# 06_-_Backlight_LEDs.net
KiCad netlist of a schematic drawn in Altium Designer
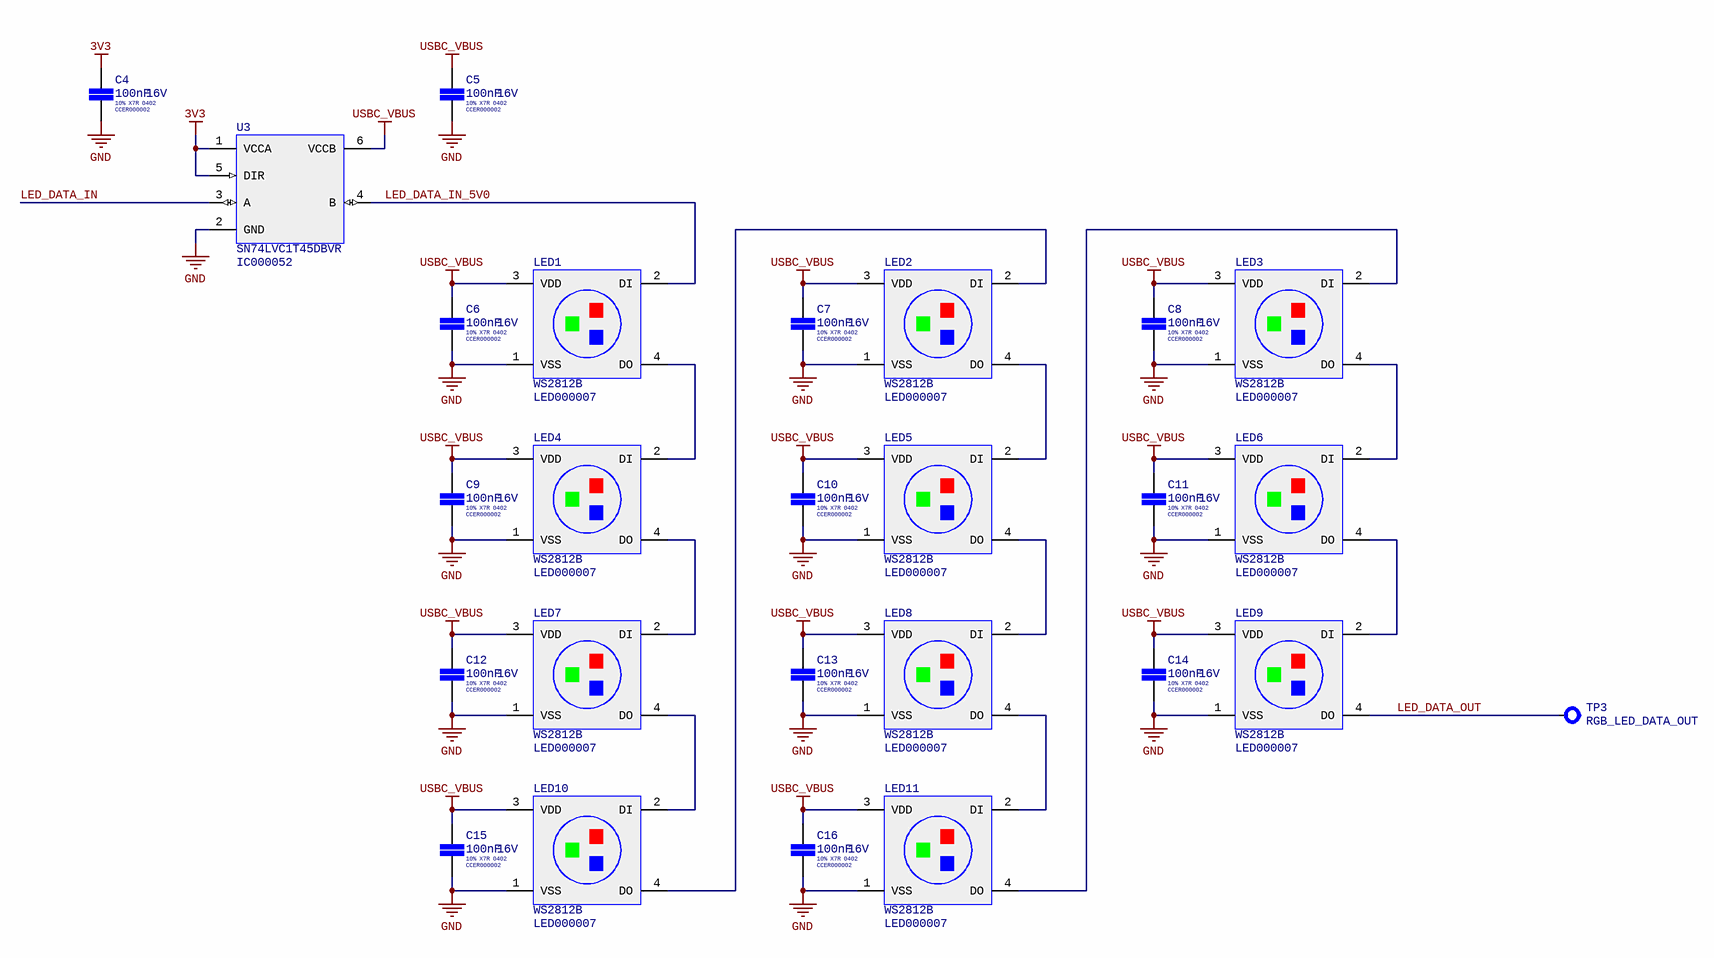
[diagram p0: [06] - Backlight LEDs.SchDoc]

(export (version "E")
  (design (tool "Eeschema 10.0.6"))
  (components
    (comp (ref "C4")
      (value "100nF 16V")
      (footprint "CAP-SMD-0402-0.55MM-IPC-MED")
      (description "CAP CER 100N 16V X7R 10% SMD 0402 125C SAMSUNG")
      (fields
        (field (name "VOLTAGE") "16V")
        (field (name "TOLERANCE") "10%")
        (field (name "INTERNAL PART NUMBER") "CCER000002")
        (field (name "VOLTAGE RATING (DC)") "16V")
        (field (name "DIELECTRIC") "X7R")
        (field (name "CASE/PACKAGE") "0402")
        (field (name "CAPACITANCE") "100nF")
      )
      (libsource (lib "Altium_Lib_Standard") (part "CL05B104KO5NNNC"))
    )
    (comp (ref "C5")
      (value "100nF 16V")
      (footprint "CAP-SMD-0402-0.55MM-IPC-MED")
      (description "CAP CER 100N 16V X7R 10% SMD 0402 125C SAMSUNG")
      (fields
        (field (name "VOLTAGE") "16V")
        (field (name "TOLERANCE") "10%")
        (field (name "INTERNAL PART NUMBER") "CCER000002")
        (field (name "VOLTAGE RATING (DC)") "16V")
        (field (name "DIELECTRIC") "X7R")
        (field (name "CASE/PACKAGE") "0402")
        (field (name "CAPACITANCE") "100nF")
      )
      (libsource (lib "Altium_Lib_Standard") (part "CL05B104KO5NNNC"))
    )
    (comp (ref "C6")
      (value "100nF 16V")
      (footprint "CAP-SMD-0402-0.55MM-IPC-MED")
      (description "CAP CER 100N 16V X7R 10% SMD 0402 125C SAMSUNG")
      (fields
        (field (name "VOLTAGE") "16V")
        (field (name "TOLERANCE") "10%")
        (field (name "INTERNAL PART NUMBER") "CCER000002")
        (field (name "VOLTAGE RATING (DC)") "16V")
        (field (name "DIELECTRIC") "X7R")
        (field (name "CASE/PACKAGE") "0402")
        (field (name "CAPACITANCE") "100nF")
      )
      (libsource (lib "Altium_Lib_Standard") (part "CL05B104KO5NNNC"))
    )
    (comp (ref "C7")
      (value "100nF 16V")
      (footprint "CAP-SMD-0402-0.55MM-IPC-MED")
      (description "CAP CER 100N 16V X7R 10% SMD 0402 125C SAMSUNG")
      (fields
        (field (name "VOLTAGE") "16V")
        (field (name "TOLERANCE") "10%")
        (field (name "INTERNAL PART NUMBER") "CCER000002")
        (field (name "VOLTAGE RATING (DC)") "16V")
        (field (name "DIELECTRIC") "X7R")
        (field (name "CASE/PACKAGE") "0402")
        (field (name "CAPACITANCE") "100nF")
      )
      (libsource (lib "Altium_Lib_Standard") (part "CL05B104KO5NNNC"))
    )
    (comp (ref "C8")
      (value "100nF 16V")
      (footprint "CAP-SMD-0402-0.55MM-IPC-MED")
      (description "CAP CER 100N 16V X7R 10% SMD 0402 125C SAMSUNG")
      (fields
        (field (name "VOLTAGE") "16V")
        (field (name "TOLERANCE") "10%")
        (field (name "INTERNAL PART NUMBER") "CCER000002")
        (field (name "VOLTAGE RATING (DC)") "16V")
        (field (name "DIELECTRIC") "X7R")
        (field (name "CASE/PACKAGE") "0402")
        (field (name "CAPACITANCE") "100nF")
      )
      (libsource (lib "Altium_Lib_Standard") (part "CL05B104KO5NNNC"))
    )
    (comp (ref "C9")
      (value "100nF 16V")
      (footprint "CAP-SMD-0402-0.55MM-IPC-MED")
      (description "CAP CER 100N 16V X7R 10% SMD 0402 125C SAMSUNG")
      (fields
        (field (name "VOLTAGE") "16V")
        (field (name "TOLERANCE") "10%")
        (field (name "INTERNAL PART NUMBER") "CCER000002")
        (field (name "VOLTAGE RATING (DC)") "16V")
        (field (name "DIELECTRIC") "X7R")
        (field (name "CASE/PACKAGE") "0402")
        (field (name "CAPACITANCE") "100nF")
      )
      (libsource (lib "Altium_Lib_Standard") (part "CL05B104KO5NNNC"))
    )
    (comp (ref "C10")
      (value "100nF 16V")
      (footprint "CAP-SMD-0402-0.55MM-IPC-MED")
      (description "CAP CER 100N 16V X7R 10% SMD 0402 125C SAMSUNG")
      (fields
        (field (name "VOLTAGE") "16V")
        (field (name "TOLERANCE") "10%")
        (field (name "INTERNAL PART NUMBER") "CCER000002")
        (field (name "VOLTAGE RATING (DC)") "16V")
        (field (name "DIELECTRIC") "X7R")
        (field (name "CASE/PACKAGE") "0402")
        (field (name "CAPACITANCE") "100nF")
      )
      (libsource (lib "Altium_Lib_Standard") (part "CL05B104KO5NNNC"))
    )
    (comp (ref "C11")
      (value "100nF 16V")
      (footprint "CAP-SMD-0402-0.55MM-IPC-MED")
      (description "CAP CER 100N 16V X7R 10% SMD 0402 125C SAMSUNG")
      (fields
        (field (name "VOLTAGE") "16V")
        (field (name "TOLERANCE") "10%")
        (field (name "INTERNAL PART NUMBER") "CCER000002")
        (field (name "VOLTAGE RATING (DC)") "16V")
        (field (name "DIELECTRIC") "X7R")
        (field (name "CASE/PACKAGE") "0402")
        (field (name "CAPACITANCE") "100nF")
      )
      (libsource (lib "Altium_Lib_Standard") (part "CL05B104KO5NNNC"))
    )
    (comp (ref "C12")
      (value "100nF 16V")
      (footprint "CAP-SMD-0402-0.55MM-IPC-MED")
      (description "CAP CER 100N 16V X7R 10% SMD 0402 125C SAMSUNG")
      (fields
        (field (name "VOLTAGE") "16V")
        (field (name "TOLERANCE") "10%")
        (field (name "INTERNAL PART NUMBER") "CCER000002")
        (field (name "VOLTAGE RATING (DC)") "16V")
        (field (name "DIELECTRIC") "X7R")
        (field (name "CASE/PACKAGE") "0402")
        (field (name "CAPACITANCE") "100nF")
      )
      (libsource (lib "Altium_Lib_Standard") (part "CL05B104KO5NNNC"))
    )
    (comp (ref "C13")
      (value "100nF 16V")
      (footprint "CAP-SMD-0402-0.55MM-IPC-MED")
      (description "CAP CER 100N 16V X7R 10% SMD 0402 125C SAMSUNG")
      (fields
        (field (name "VOLTAGE") "16V")
        (field (name "TOLERANCE") "10%")
        (field (name "INTERNAL PART NUMBER") "CCER000002")
        (field (name "VOLTAGE RATING (DC)") "16V")
        (field (name "DIELECTRIC") "X7R")
        (field (name "CASE/PACKAGE") "0402")
        (field (name "CAPACITANCE") "100nF")
      )
      (libsource (lib "Altium_Lib_Standard") (part "CL05B104KO5NNNC"))
    )
    (comp (ref "C14")
      (value "100nF 16V")
      (footprint "CAP-SMD-0402-0.55MM-IPC-MED")
      (description "CAP CER 100N 16V X7R 10% SMD 0402 125C SAMSUNG")
      (fields
        (field (name "VOLTAGE") "16V")
        (field (name "TOLERANCE") "10%")
        (field (name "INTERNAL PART NUMBER") "CCER000002")
        (field (name "VOLTAGE RATING (DC)") "16V")
        (field (name "DIELECTRIC") "X7R")
        (field (name "CASE/PACKAGE") "0402")
        (field (name "CAPACITANCE") "100nF")
      )
      (libsource (lib "Altium_Lib_Standard") (part "CL05B104KO5NNNC"))
    )
    (comp (ref "C15")
      (value "100nF 16V")
      (footprint "CAP-SMD-0402-0.55MM-IPC-MED")
      (description "CAP CER 100N 16V X7R 10% SMD 0402 125C SAMSUNG")
      (fields
        (field (name "VOLTAGE") "16V")
        (field (name "TOLERANCE") "10%")
        (field (name "INTERNAL PART NUMBER") "CCER000002")
        (field (name "VOLTAGE RATING (DC)") "16V")
        (field (name "DIELECTRIC") "X7R")
        (field (name "CASE/PACKAGE") "0402")
        (field (name "CAPACITANCE") "100nF")
      )
      (libsource (lib "Altium_Lib_Standard") (part "CL05B104KO5NNNC"))
    )
    (comp (ref "C16")
      (value "100nF 16V")
      (footprint "CAP-SMD-0402-0.55MM-IPC-MED")
      (description "CAP CER 100N 16V X7R 10% SMD 0402 125C SAMSUNG")
      (fields
        (field (name "VOLTAGE") "16V")
        (field (name "TOLERANCE") "10%")
        (field (name "INTERNAL PART NUMBER") "CCER000002")
        (field (name "VOLTAGE RATING (DC)") "16V")
        (field (name "DIELECTRIC") "X7R")
        (field (name "CASE/PACKAGE") "0402")
        (field (name "CAPACITANCE") "100nF")
      )
      (libsource (lib "Altium_Lib_Standard") (part "CL05B104KO5NNNC"))
    )
    (comp (ref "LED1")
      (value "WS2812B")
      (footprint "LED-SMD-4-SMD-5050-WS2812B")
      (description "LED RGB-ADDRESSABLE SERIAL 5050")
      (fields (field (name "INTERNAL PART NUMBER") "LED000007"))
      (libsource (lib "Altium_Lib_Standard") (part "WS2812B"))
    )
    (comp (ref "LED2")
      (value "WS2812B")
      (footprint "LED-SMD-4-SMD-5050-WS2812B")
      (description "LED RGB-ADDRESSABLE SERIAL 5050")
      (fields (field (name "INTERNAL PART NUMBER") "LED000007"))
      (libsource (lib "Altium_Lib_Standard") (part "WS2812B"))
    )
    (comp (ref "LED3")
      (value "WS2812B")
      (footprint "LED-SMD-4-SMD-5050-WS2812B")
      (description "LED RGB-ADDRESSABLE SERIAL 5050")
      (fields (field (name "INTERNAL PART NUMBER") "LED000007"))
      (libsource (lib "Altium_Lib_Standard") (part "WS2812B"))
    )
    (comp (ref "LED4")
      (value "WS2812B")
      (footprint "LED-SMD-4-SMD-5050-WS2812B")
      (description "LED RGB-ADDRESSABLE SERIAL 5050")
      (fields (field (name "INTERNAL PART NUMBER") "LED000007"))
      (libsource (lib "Altium_Lib_Standard") (part "WS2812B"))
    )
    (comp (ref "LED5")
      (value "WS2812B")
      (footprint "LED-SMD-4-SMD-5050-WS2812B")
      (description "LED RGB-ADDRESSABLE SERIAL 5050")
      (fields (field (name "INTERNAL PART NUMBER") "LED000007"))
      (libsource (lib "Altium_Lib_Standard") (part "WS2812B"))
    )
    (comp (ref "LED6")
      (value "WS2812B")
      (footprint "LED-SMD-4-SMD-5050-WS2812B")
      (description "LED RGB-ADDRESSABLE SERIAL 5050")
      (fields (field (name "INTERNAL PART NUMBER") "LED000007"))
      (libsource (lib "Altium_Lib_Standard") (part "WS2812B"))
    )
    (comp (ref "LED7")
      (value "WS2812B")
      (footprint "LED-SMD-4-SMD-5050-WS2812B")
      (description "LED RGB-ADDRESSABLE SERIAL 5050")
      (fields (field (name "INTERNAL PART NUMBER") "LED000007"))
      (libsource (lib "Altium_Lib_Standard") (part "WS2812B"))
    )
    (comp (ref "LED8")
      (value "WS2812B")
      (footprint "LED-SMD-4-SMD-5050-WS2812B")
      (description "LED RGB-ADDRESSABLE SERIAL 5050")
      (fields (field (name "INTERNAL PART NUMBER") "LED000007"))
      (libsource (lib "Altium_Lib_Standard") (part "WS2812B"))
    )
    (comp (ref "LED9")
      (value "WS2812B")
      (footprint "LED-SMD-4-SMD-5050-WS2812B")
      (description "LED RGB-ADDRESSABLE SERIAL 5050")
      (fields (field (name "INTERNAL PART NUMBER") "LED000007"))
      (libsource (lib "Altium_Lib_Standard") (part "WS2812B"))
    )
    (comp (ref "LED10")
      (value "WS2812B")
      (footprint "LED-SMD-4-SMD-5050-WS2812B")
      (description "LED RGB-ADDRESSABLE SERIAL 5050")
      (fields (field (name "INTERNAL PART NUMBER") "LED000007"))
      (libsource (lib "Altium_Lib_Standard") (part "WS2812B"))
    )
    (comp (ref "LED11")
      (value "WS2812B")
      (footprint "LED-SMD-4-SMD-5050-WS2812B")
      (description "LED RGB-ADDRESSABLE SERIAL 5050")
      (fields (field (name "INTERNAL PART NUMBER") "LED000007"))
      (libsource (lib "Altium_Lib_Standard") (part "WS2812B"))
    )
    (comp (ref "TP3")
      (value "RGB_LED_DATA_OUT")
      (footprint "TP-SMD-CIRCULAR-1MM")
      (libsource (lib "Altium_Lib_Standard") (part "TESTPOINT_CIRCULAR_1MM"))
    )
    (comp (ref "U3")
      (value "SN74LVC1T45DBVR")
      (footprint "SOT-23-6-H1.45MM-TI")
      (description "IC LEVEL SHIFTER BIDIR TRISTATE 1CH SOT-23-6 1V65-5V5")
      (fields
        (field (name "MANUFACTURER") "Texas Instruments")
        (field (name "INTERNAL PART NUMBER") "IC000052")
      )
      (libsource (lib "Altium_Lib_Standard") (part "SN74LVC1T45DBVR"))
    )
  )
  (nets
    (net (code "1") (name "/LED_DATA_IN") (class "Default")
      (node (ref "U3") (pin "3") (pinfunction "A_3") (pintype "bidirectional"))
    )
    (net (code "2") (name "/LED_DATA_IN_5V0") (class "Default")
      (node (ref "LED1") (pin "2") (pinfunction "DI_2") (pintype "passive"))
      (node (ref "U3") (pin "4") (pinfunction "B_4") (pintype "bidirectional"))
    )
    (net (code "3") (name "/LED_DATA_OUT") (class "Default")
      (node (ref "LED9") (pin "4") (pinfunction "DO_4") (pintype "passive"))
      (node (ref "TP3") (pin "1") (pinfunction "1_1") (pintype "passive"))
    )
    (net (code "4") (name "3V3") (class "Default")
      (node (ref "C4") (pin "1") (pinfunction "1_1") (pintype "passive"))
      (node (ref "U3") (pin "1") (pinfunction "VCCA_1") (pintype "power_in"))
      (node (ref "U3") (pin "5") (pinfunction "DIR_5") (pintype "input"))
    )
    (net (code "5") (name "GND") (class "Default")
      (node (ref "C10") (pin "2") (pinfunction "2_2") (pintype "passive"))
      (node (ref "C11") (pin "2") (pinfunction "2_2") (pintype "passive"))
      (node (ref "C12") (pin "2") (pinfunction "2_2") (pintype "passive"))
      (node (ref "C13") (pin "2") (pinfunction "2_2") (pintype "passive"))
      (node (ref "C14") (pin "2") (pinfunction "2_2") (pintype "passive"))
      (node (ref "C15") (pin "2") (pinfunction "2_2") (pintype "passive"))
      (node (ref "C16") (pin "2") (pinfunction "2_2") (pintype "passive"))
      (node (ref "C4") (pin "2") (pinfunction "2_2") (pintype "passive"))
      (node (ref "C5") (pin "2") (pinfunction "2_2") (pintype "passive"))
      (node (ref "C6") (pin "2") (pinfunction "2_2") (pintype "passive"))
      (node (ref "C7") (pin "2") (pinfunction "2_2") (pintype "passive"))
      (node (ref "C8") (pin "2") (pinfunction "2_2") (pintype "passive"))
      (node (ref "C9") (pin "2") (pinfunction "2_2") (pintype "passive"))
      (node (ref "LED1") (pin "1") (pinfunction "VSS_1") (pintype "passive"))
      (node (ref "LED10") (pin "1") (pinfunction "VSS_1") (pintype "passive"))
      (node (ref "LED11") (pin "1") (pinfunction "VSS_1") (pintype "passive"))
      (node (ref "LED2") (pin "1") (pinfunction "VSS_1") (pintype "passive"))
      (node (ref "LED3") (pin "1") (pinfunction "VSS_1") (pintype "passive"))
      (node (ref "LED4") (pin "1") (pinfunction "VSS_1") (pintype "passive"))
      (node (ref "LED5") (pin "1") (pinfunction "VSS_1") (pintype "passive"))
      (node (ref "LED6") (pin "1") (pinfunction "VSS_1") (pintype "passive"))
      (node (ref "LED7") (pin "1") (pinfunction "VSS_1") (pintype "passive"))
      (node (ref "LED8") (pin "1") (pinfunction "VSS_1") (pintype "passive"))
      (node (ref "LED9") (pin "1") (pinfunction "VSS_1") (pintype "passive"))
      (node (ref "U3") (pin "2") (pinfunction "GND_2") (pintype "power_in"))
    )
    (net (code "6") (name "Net-(LED1-DO)") (class "Default")
      (node (ref "LED1") (pin "4") (pinfunction "DO_4") (pintype "passive"))
      (node (ref "LED4") (pin "2") (pinfunction "DI_2") (pintype "passive"))
    )
    (net (code "7") (name "Net-(LED2-DO)") (class "Default")
      (node (ref "LED2") (pin "4") (pinfunction "DO_4") (pintype "passive"))
      (node (ref "LED5") (pin "2") (pinfunction "DI_2") (pintype "passive"))
    )
    (net (code "8") (name "Net-(LED3-DO)") (class "Default")
      (node (ref "LED3") (pin "4") (pinfunction "DO_4") (pintype "passive"))
      (node (ref "LED6") (pin "2") (pinfunction "DI_2") (pintype "passive"))
    )
    (net (code "9") (name "Net-(LED4-DO)") (class "Default")
      (node (ref "LED4") (pin "4") (pinfunction "DO_4") (pintype "passive"))
      (node (ref "LED7") (pin "2") (pinfunction "DI_2") (pintype "passive"))
    )
    (net (code "10") (name "Net-(LED5-DO)") (class "Default")
      (node (ref "LED5") (pin "4") (pinfunction "DO_4") (pintype "passive"))
      (node (ref "LED8") (pin "2") (pinfunction "DI_2") (pintype "passive"))
    )
    (net (code "11") (name "Net-(LED6-DO)") (class "Default")
      (node (ref "LED6") (pin "4") (pinfunction "DO_4") (pintype "passive"))
      (node (ref "LED9") (pin "2") (pinfunction "DI_2") (pintype "passive"))
    )
    (net (code "12") (name "Net-(LED10-DI)") (class "Default")
      (node (ref "LED10") (pin "2") (pinfunction "DI_2") (pintype "passive"))
      (node (ref "LED7") (pin "4") (pinfunction "DO_4") (pintype "passive"))
    )
    (net (code "13") (name "Net-(LED10-DO)") (class "Default")
      (node (ref "LED10") (pin "4") (pinfunction "DO_4") (pintype "passive"))
      (node (ref "LED2") (pin "2") (pinfunction "DI_2") (pintype "passive"))
    )
    (net (code "14") (name "Net-(LED11-DI)") (class "Default")
      (node (ref "LED11") (pin "2") (pinfunction "DI_2") (pintype "passive"))
      (node (ref "LED8") (pin "4") (pinfunction "DO_4") (pintype "passive"))
    )
    (net (code "15") (name "Net-(LED11-DO)") (class "Default")
      (node (ref "LED11") (pin "4") (pinfunction "DO_4") (pintype "passive"))
      (node (ref "LED3") (pin "2") (pinfunction "DI_2") (pintype "passive"))
    )
    (net (code "16") (name "USBC_VBUS") (class "Default")
      (node (ref "C10") (pin "1") (pinfunction "1_1") (pintype "passive"))
      (node (ref "C11") (pin "1") (pinfunction "1_1") (pintype "passive"))
      (node (ref "C12") (pin "1") (pinfunction "1_1") (pintype "passive"))
      (node (ref "C13") (pin "1") (pinfunction "1_1") (pintype "passive"))
      (node (ref "C14") (pin "1") (pinfunction "1_1") (pintype "passive"))
      (node (ref "C15") (pin "1") (pinfunction "1_1") (pintype "passive"))
      (node (ref "C16") (pin "1") (pinfunction "1_1") (pintype "passive"))
      (node (ref "C5") (pin "1") (pinfunction "1_1") (pintype "passive"))
      (node (ref "C6") (pin "1") (pinfunction "1_1") (pintype "passive"))
      (node (ref "C7") (pin "1") (pinfunction "1_1") (pintype "passive"))
      (node (ref "C8") (pin "1") (pinfunction "1_1") (pintype "passive"))
      (node (ref "C9") (pin "1") (pinfunction "1_1") (pintype "passive"))
      (node (ref "LED1") (pin "3") (pinfunction "VDD_3") (pintype "passive"))
      (node (ref "LED10") (pin "3") (pinfunction "VDD_3") (pintype "passive"))
      (node (ref "LED11") (pin "3") (pinfunction "VDD_3") (pintype "passive"))
      (node (ref "LED2") (pin "3") (pinfunction "VDD_3") (pintype "passive"))
      (node (ref "LED3") (pin "3") (pinfunction "VDD_3") (pintype "passive"))
      (node (ref "LED4") (pin "3") (pinfunction "VDD_3") (pintype "passive"))
      (node (ref "LED5") (pin "3") (pinfunction "VDD_3") (pintype "passive"))
      (node (ref "LED6") (pin "3") (pinfunction "VDD_3") (pintype "passive"))
      (node (ref "LED7") (pin "3") (pinfunction "VDD_3") (pintype "passive"))
      (node (ref "LED8") (pin "3") (pinfunction "VDD_3") (pintype "passive"))
      (node (ref "LED9") (pin "3") (pinfunction "VDD_3") (pintype "passive"))
      (node (ref "U3") (pin "6") (pinfunction "VCCB_6") (pintype "power_in"))
    )
  )
)
